# IMX7S_SENSORS___EXTERNAL_INTERFACES.net
KiCad netlist of a schematic drawn in Altium Designer
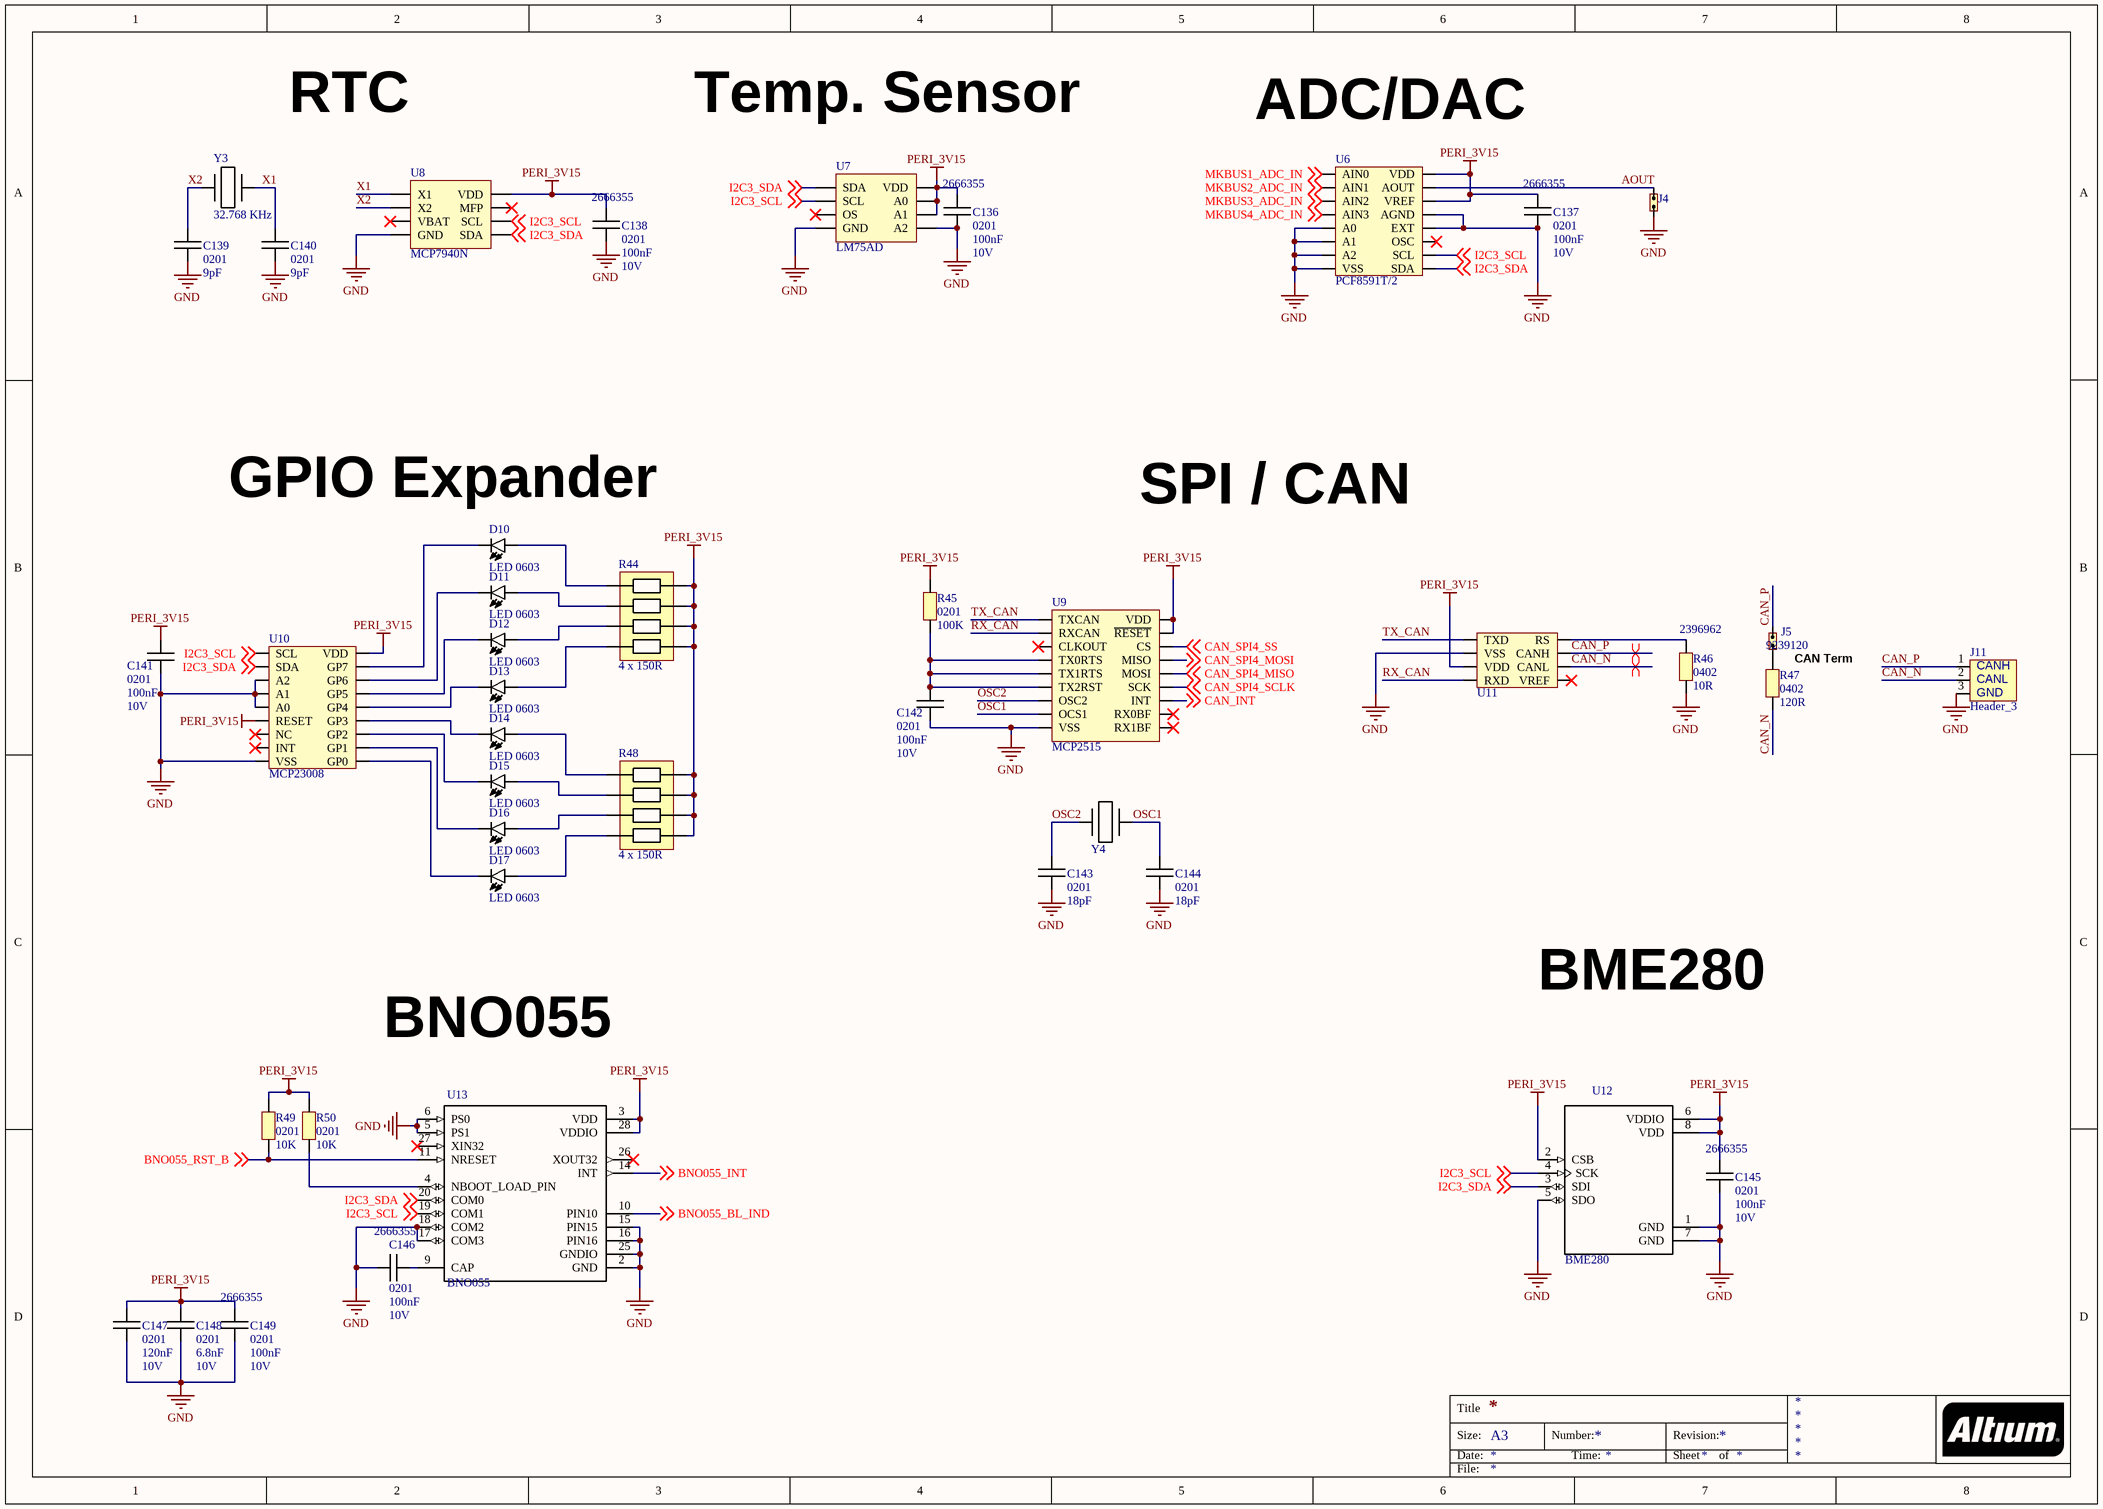
[diagram p0: IMX7S_SENSORS_&_EXTERNAL_INTERFACES.SchDoc]

(export (version "E")
  (design (tool "Eeschema 10.0.6"))
  (components
    (comp (ref "C136")
      (value "100nF")
      (footprint "C0201")
      (fields
        (field (name "PACKAGE") "0201")
        (field (name "VOLTAGE") "10V")
        (field (name "SUPPLIER PART NUMBER 1") "2666355")
        (field (name "TOLERANCE") "10%")
        (field (name "Comment") "C0201")
      )
      (libsource (lib "Schlib_IMX7") (part "C0201"))
    )
    (comp (ref "C137")
      (value "100nF")
      (footprint "C0201")
      (fields
        (field (name "PACKAGE") "0201")
        (field (name "VOLTAGE") "10V")
        (field (name "SUPPLIER PART NUMBER 1") "2666355")
        (field (name "TOLERANCE") "10%")
        (field (name "Comment") "C0201")
      )
      (libsource (lib "Schlib_IMX7") (part "C0201"))
    )
    (comp (ref "C138")
      (value "100nF")
      (footprint "C0201")
      (fields
        (field (name "PACKAGE") "0201")
        (field (name "VOLTAGE") "10V")
        (field (name "SUPPLIER PART NUMBER 1") "2666355")
        (field (name "TOLERANCE") "10%")
        (field (name "Comment") "C0201")
      )
      (libsource (lib "Schlib_IMX7") (part "C0201"))
    )
    (comp (ref "C139")
      (value "9pF")
      (footprint "C0201")
      (description "CAP CER 9PF 25V C0G 0201")
      (fields (field (name "PACKAGE") "0201") (field (name "VOLTAGE") "0V") (field (name "Comment") "C0201"))
      (libsource (lib "Schlib_IMX7") (part "C0201"))
    )
    (comp (ref "C140")
      (value "9pF")
      (footprint "C0201")
      (description "CAP CER 9PF 25V C0G 0201")
      (fields (field (name "PACKAGE") "0201") (field (name "VOLTAGE") "0V") (field (name "Comment") "C0201"))
      (libsource (lib "Schlib_IMX7") (part "C0201"))
    )
    (comp (ref "C141")
      (value "100nF")
      (footprint "C0201")
      (fields (field (name "PACKAGE") "0201") (field (name "VOLTAGE") "10V") (field (name "Comment") "C0201"))
      (libsource (lib "Schlib_IMX7") (part "C0201"))
    )
    (comp (ref "C142")
      (value "100nF")
      (footprint "C0201")
      (fields (field (name "PACKAGE") "0201") (field (name "VOLTAGE") "10V") (field (name "Comment") "C0201"))
      (libsource (lib "Schlib_IMX7") (part "C0201"))
    )
    (comp (ref "C143")
      (value "18pF")
      (footprint "C0201")
      (description "0201 18 pF 50 V ±2% Tolerance C0G/NP0 Multilayer Ceramic Capacitor")
      (fields (field (name "PACKAGE") "0201") (field (name "VOLTAGE") "10V") (field (name "TOLERANCE") "2%"))
      (libsource (lib "Schlib_IMX7") (part "C0201"))
    )
    (comp (ref "C144")
      (value "18pF")
      (footprint "C0201")
      (description "0201 18 pF 50 V ±2% Tolerance C0G/NP0 Multilayer Ceramic Capacitor")
      (fields (field (name "PACKAGE") "0201") (field (name "VOLTAGE") "10V") (field (name "TOLERANCE") "2%"))
      (libsource (lib "Schlib_IMX7") (part "C0201"))
    )
    (comp (ref "C145")
      (value "100nF")
      (footprint "C0201")
      (fields
        (field (name "PACKAGE") "0201")
        (field (name "VOLTAGE") "10V")
        (field (name "SUPPLIER PART NUMBER 1") "2666355")
        (field (name "TOLERANCE") "10%")
        (field (name "Comment") "C0201")
      )
      (libsource (lib "Schlib_IMX7") (part "C0201"))
    )
    (comp (ref "C146")
      (value "100nF")
      (footprint "C0201")
      (fields
        (field (name "PACKAGE") "0201")
        (field (name "VOLTAGE") "10V")
        (field (name "SUPPLIER PART NUMBER 1") "2666355")
        (field (name "TOLERANCE") "10%")
        (field (name "Comment") "C0201")
      )
      (libsource (lib "Schlib_IMX7") (part "C0201"))
    )
    (comp (ref "C147")
      (value "120nF")
      (footprint "C0201")
      (fields (field (name "PACKAGE") "0201") (field (name "VOLTAGE") "10V") (field (name "Comment") "C0201"))
      (libsource (lib "Schlib_IMX7") (part "C0201"))
    )
    (comp (ref "C148")
      (value "6.8nF")
      (footprint "C0201")
      (fields (field (name "PACKAGE") "0201") (field (name "VOLTAGE") "10V") (field (name "Comment") "C0201"))
      (libsource (lib "Schlib_IMX7") (part "C0201"))
    )
    (comp (ref "C149")
      (value "100nF")
      (footprint "C0201")
      (fields
        (field (name "PACKAGE") "0201")
        (field (name "VOLTAGE") "10V")
        (field (name "SUPPLIER PART NUMBER 1") "2666355")
        (field (name "TOLERANCE") "10%")
        (field (name "Comment") "C0201")
      )
      (libsource (lib "Schlib_IMX7") (part "C0201"))
    )
    (comp (ref "D10") (value "LED 0603") (footprint "D0603") (libsource (lib "Schlib_IMX7") (part "LED")))
    (comp (ref "D11") (value "LED 0603") (footprint "D0603") (libsource (lib "Schlib_IMX7") (part "LED")))
    (comp (ref "D12") (value "LED 0603") (footprint "D0603") (libsource (lib "Schlib_IMX7") (part "LED")))
    (comp (ref "D13") (value "LED 0603") (footprint "D0603") (libsource (lib "Schlib_IMX7") (part "LED")))
    (comp (ref "D14") (value "LED 0603") (footprint "D0603") (libsource (lib "Schlib_IMX7") (part "LED")))
    (comp (ref "D15") (value "LED 0603") (footprint "D0603") (libsource (lib "Schlib_IMX7") (part "LED")))
    (comp (ref "D16") (value "LED 0603") (footprint "D0603") (libsource (lib "Schlib_IMX7") (part "LED")))
    (comp (ref "D17") (value "LED 0603") (footprint "D0603") (libsource (lib "Schlib_IMX7") (part "LED")))
    (comp (ref "J4") (value "Jumper") (footprint "Header 2") (libsource (lib "Schlib_IMX7") (part "Jumper")))
    (comp (ref "J5") (value "Jumper") (footprint "Header 2") (libsource (lib "Schlib_IMX7") (part "Jumper")))
    (comp (ref "J11")
      (value "Header_3")
      (footprint "Header 3")
      (libsource (lib "Schlib_IMX7") (part "Header_3"))
    )
    (comp (ref "R44")
      (value "4 x 150R")
      (footprint "Reseau_R_1206")
      (libsource (lib "Schlib_IMX7") (part "Reseau_res"))
    )
    (comp (ref "R45")
      (value "100K")
      (footprint "R0201")
      (fields (field (name "PACKAGE") "0201") (field (name "VOLTAGE") "0V") (field (name "Comment") "R0201"))
      (libsource (lib "Schlib_IMX7") (part "R0201"))
    )
    (comp (ref "R46")
      (value "10R")
      (footprint "R0402")
      (fields
        (field (name "PACKAGE") "0402")
        (field (name "VOLTAGE") "0V")
        (field (name "SUPPLIER PART NUMBER 1") "2396962")
        (field (name "TOLERANCE") "1%")
        (field (name "Comment") "R0402")
      )
      (libsource (lib "Schlib_IMX7") (part "R0402"))
    )
    (comp (ref "R47")
      (value "120R")
      (footprint "R0402")
      (fields
        (field (name "PACKAGE") "0402")
        (field (name "VOLTAGE") "0V")
        (field (name "SUPPLIER PART NUMBER 1") "9239120")
        (field (name "TOLERANCE") "1%")
        (field (name "Comment") "R0402")
      )
      (libsource (lib "") (part "R0402_1"))
    )
    (comp (ref "R48")
      (value "4 x 150R")
      (footprint "Reseau_R_1206")
      (libsource (lib "Schlib_IMX7") (part "Reseau_res"))
    )
    (comp (ref "R49")
      (value "10K")
      (footprint "R0201")
      (fields (field (name "PACKAGE") "0201") (field (name "VOLTAGE") "0V") (field (name "Comment") "R0201"))
      (libsource (lib "Schlib_IMX7") (part "R0201"))
    )
    (comp (ref "R50")
      (value "10K")
      (footprint "R0201")
      (fields (field (name "PACKAGE") "0201") (field (name "VOLTAGE") "0V") (field (name "Comment") "R0201"))
      (libsource (lib "Schlib_IMX7") (part "R0201"))
    )
    (comp (ref "U6")
      (value "PCF8591T/2")
      (footprint "SOIC 16")
      (libsource (lib "Schlib_IMX7") (part "PCF8591T/2"))
    )
    (comp (ref "U7") (value "LM75AD") (footprint "SOIC 8") (libsource (lib "Schlib_IMX7") (part "LM75AD")))
    (comp (ref "U8")
      (value "MCP7940N")
      (footprint "SOIC 8")
      (libsource (lib "Schlib_IMX7") (part "MCP7940N"))
    )
    (comp (ref "U9") (value "MCP2515") (footprint "SOIC 18") (libsource (lib "Schlib_IMX7") (part "MCP2515")))
    (comp (ref "U10")
      (value "MCP23008")
      (footprint "SOIC 18")
      (libsource (lib "Schlib_IMX7") (part "MCP23008"))
    )
    (comp (ref "U11")
      (value "SN65HVD230DR")
      (footprint "SOIC 8")
      (libsource (lib "Schlib_IMX7") (part "SN65HVD230DR"))
    )
    (comp (ref "U12")
      (value "BME280")
      (footprint "PSON65P250X250X100-8N")
      (description "Integrated pressure, humidity and temperature sensor; 8-pin 2.5x2.5x0.93mm LGA")
      (fields (field (name "MF") "Bosch"))
      (libsource (lib "Schlib_IMX7") (part "BME280"))
    )
    (comp (ref "U13")
      (value "BNO055")
      (footprint "LGA28R50P4X10_380X520X100")
      (description "BNO055 9-axis Absolute Orientation Sensor _ SiP _ w/Sensors and Sensor Fusion")
      (fields (field (name "MF") "Bosch"))
      (libsource (lib "Schlib_IMX7") (part "BNO055"))
    )
    (comp (ref "Y3")
      (value "32.768 KHz")
      (footprint "ABS07")
      (libsource (lib "Schlib_IMX7") (part "Quartz 32.768"))
    )
    (comp (ref "Y4")
      (value "Quartz 8MHz")
      (footprint "HC49")
      (libsource (lib "Schlib_IMX7") (part "Quartz 8MHz"))
    )
  )
  (nets
    (net (code "1") (name "/AOUT") (class "Default")
      (node (ref "J4") (pin "2") (pinfunction "2_2") (pintype "passive"))
      (node (ref "U6") (pin "15") (pinfunction "AOUT_15") (pintype "passive"))
    )
    (net (code "2") (name "/CAN_N") (class "Default")
      (node (ref "J11") (pin "2") (pinfunction "2_2") (pintype "passive"))
      (node (ref "R47") (pin "1") (pinfunction "1_1") (pintype "passive"))
      (node (ref "U11") (pin "6") (pinfunction "CANL_6") (pintype "passive"))
    )
    (net (code "3") (name "/CAN_P") (class "Default")
      (node (ref "J11") (pin "1") (pinfunction "1_1") (pintype "passive"))
      (node (ref "J5") (pin "2") (pinfunction "2_2") (pintype "passive"))
      (node (ref "U11") (pin "7") (pinfunction "CANH_7") (pintype "passive"))
    )
    (net (code "4") (name "/OSC1") (class "Default")
      (node (ref "C144") (pin "2") (pinfunction "2_2") (pintype "passive"))
      (node (ref "U9") (pin "8") (pinfunction "OCS1_8") (pintype "passive"))
      (node (ref "Y4") (pin "2") (pintype "passive"))
    )
    (net (code "5") (name "/OSC2") (class "Default")
      (node (ref "C143") (pin "2") (pinfunction "2_2") (pintype "passive"))
      (node (ref "U9") (pin "7") (pinfunction "OSC2_7") (pintype "passive"))
      (node (ref "Y4") (pin "1") (pintype "passive"))
    )
    (net (code "6") (name "/RX_CAN") (class "Default")
      (node (ref "U11") (pin "4") (pinfunction "RXD_4") (pintype "passive"))
      (node (ref "U9") (pin "2") (pinfunction "RXCAN_2") (pintype "passive"))
    )
    (net (code "7") (name "/TX_CAN") (class "Default")
      (node (ref "U11") (pin "1") (pinfunction "TXD_1") (pintype "passive"))
      (node (ref "U9") (pin "1") (pinfunction "TXCAN_1") (pintype "passive"))
    )
    (net (code "8") (name "/X1") (class "Default")
      (node (ref "C140") (pin "2") (pinfunction "2_2") (pintype "passive"))
      (node (ref "U8") (pin "1") (pinfunction "X1_1") (pintype "passive"))
      (node (ref "Y3") (pin "2") (pintype "passive"))
    )
    (net (code "9") (name "/X2") (class "Default")
      (node (ref "C139") (pin "2") (pinfunction "2_2") (pintype "passive"))
      (node (ref "U8") (pin "2") (pinfunction "X2_2") (pintype "passive"))
      (node (ref "Y3") (pin "1") (pintype "passive"))
    )
    (net (code "10") (name "BNO055_BL_IND") (class "Default")
      (node (ref "U13") (pin "10") (pinfunction "PIN10_10") (pintype "power_in"))
    )
    (net (code "11") (name "BNO055_INT") (class "Default")
      (node (ref "U13") (pin "14") (pinfunction "INT_14") (pintype "output"))
    )
    (net (code "12") (name "BNO055_RST_B") (class "Default")
      (node (ref "R49") (pin "1") (pinfunction "1_1") (pintype "passive"))
      (node (ref "U13") (pin "11") (pinfunction "NRESET_11") (pintype "input"))
    )
    (net (code "13") (name "CAN_INT") (class "Default")
      (node (ref "U9") (pin "12") (pinfunction "INT_12") (pintype "passive"))
    )
    (net (code "14") (name "CAN_SPI4_MISO") (class "Default")
      (node (ref "U9") (pin "14") (pinfunction "MOSI_14") (pintype "passive"))
    )
    (net (code "15") (name "CAN_SPI4_MOSI") (class "Default")
      (node (ref "U9") (pin "15") (pinfunction "MISO_15") (pintype "passive"))
    )
    (net (code "16") (name "CAN_SPI4_SCLK") (class "Default")
      (node (ref "U9") (pin "13") (pinfunction "SCK_13") (pintype "passive"))
    )
    (net (code "17") (name "CAN_SPI4_SS") (class "Default")
      (node (ref "U9") (pin "16") (pinfunction "CS_16") (pintype "passive"))
    )
    (net (code "18") (name "GND") (class "Default")
      (node (ref "C136") (pin "2") (pinfunction "2_2") (pintype "passive"))
      (node (ref "C137") (pin "2") (pinfunction "2_2") (pintype "passive"))
      (node (ref "C138") (pin "2") (pinfunction "2_2") (pintype "passive"))
      (node (ref "C139") (pin "1") (pinfunction "1_1") (pintype "passive"))
      (node (ref "C140") (pin "1") (pinfunction "1_1") (pintype "passive"))
      (node (ref "C141") (pin "2") (pinfunction "2_2") (pintype "passive"))
      (node (ref "C142") (pin "2") (pinfunction "2_2") (pintype "passive"))
      (node (ref "C143") (pin "1") (pinfunction "1_1") (pintype "passive"))
      (node (ref "C144") (pin "1") (pinfunction "1_1") (pintype "passive"))
      (node (ref "C145") (pin "1") (pinfunction "1_1") (pintype "passive"))
      (node (ref "C146") (pin "2") (pinfunction "2_2") (pintype "passive"))
      (node (ref "C147") (pin "2") (pinfunction "2_2") (pintype "passive"))
      (node (ref "C148") (pin "2") (pinfunction "2_2") (pintype "passive"))
      (node (ref "C149") (pin "2") (pinfunction "2_2") (pintype "passive"))
      (node (ref "J11") (pin "3") (pinfunction "3_3") (pintype "passive"))
      (node (ref "J4") (pin "1") (pinfunction "1_1") (pintype "passive"))
      (node (ref "R46") (pin "2") (pinfunction "2_2") (pintype "passive"))
      (node (ref "U10") (pin "3") (pinfunction "A2_3") (pintype "passive"))
      (node (ref "U10") (pin "4") (pinfunction "A1_4") (pintype "passive"))
      (node (ref "U10") (pin "5") (pinfunction "A0_5") (pintype "passive"))
      (node (ref "U10") (pin "9") (pinfunction "VSS_9") (pintype "passive"))
      (node (ref "U11") (pin "2") (pinfunction "VSS_2") (pintype "passive"))
      (node (ref "U12") (pin "1") (pinfunction "GND_1") (pintype "power_in"))
      (node (ref "U12") (pin "5") (pinfunction "SDO_5") (pintype "bidirectional"))
      (node (ref "U12") (pin "7") (pinfunction "GND_7") (pintype "power_in"))
      (node (ref "U13") (pin "15") (pinfunction "PIN15_15") (pintype "power_in"))
      (node (ref "U13") (pin "16") (pinfunction "PIN16_16") (pintype "power_in"))
      (node (ref "U13") (pin "17") (pinfunction "COM3_17") (pintype "bidirectional"))
      (node (ref "U13") (pin "18") (pinfunction "COM2_18") (pintype "bidirectional"))
      (node (ref "U13") (pin "2") (pinfunction "GND_2") (pintype "power_in"))
      (node (ref "U13") (pin "25") (pinfunction "GNDIO_25") (pintype "power_in"))
      (node (ref "U13") (pin "5") (pinfunction "PS1_5") (pintype "input"))
      (node (ref "U13") (pin "6") (pinfunction "PS0_6") (pintype "input"))
      (node (ref "U6") (pin "12") (pinfunction "EXT_12") (pintype "passive"))
      (node (ref "U6") (pin "13") (pinfunction "AGND_13") (pintype "passive"))
      (node (ref "U6") (pin "5") (pinfunction "A0_5") (pintype "passive"))
      (node (ref "U6") (pin "6") (pinfunction "A1_6") (pintype "passive"))
      (node (ref "U6") (pin "7") (pinfunction "A2_7") (pintype "passive"))
      (node (ref "U6") (pin "8") (pinfunction "VSS_8") (pintype "passive"))
      (node (ref "U7") (pin "4") (pinfunction "GND_4") (pintype "passive"))
      (node (ref "U7") (pin "5") (pinfunction "A2_5") (pintype "passive"))
      (node (ref "U8") (pin "4") (pinfunction "GND_4") (pintype "passive"))
      (node (ref "U9") (pin "9") (pinfunction "VSS_9") (pintype "passive"))
    )
    (net (code "19") (name "I2C3_SCL") (class "Default")
      (node (ref "U10") (pin "1") (pinfunction "SCL_1") (pintype "passive"))
      (node (ref "U12") (pin "4") (pinfunction "SCK_4") (pintype "input"))
      (node (ref "U13") (pin "19") (pinfunction "COM1_19") (pintype "bidirectional"))
      (node (ref "U6") (pin "10") (pinfunction "SCL_10") (pintype "passive"))
      (node (ref "U7") (pin "2") (pinfunction "SCL_2") (pintype "passive"))
      (node (ref "U8") (pin "6") (pinfunction "SCL_6") (pintype "passive"))
    )
    (net (code "20") (name "I2C3_SDA") (class "Default")
      (node (ref "U10") (pin "2") (pinfunction "SDA_2") (pintype "passive"))
      (node (ref "U12") (pin "3") (pinfunction "SDI_3") (pintype "bidirectional"))
      (node (ref "U13") (pin "20") (pinfunction "COM0_20") (pintype "bidirectional"))
      (node (ref "U6") (pin "9") (pinfunction "SDA_9") (pintype "passive"))
      (node (ref "U7") (pin "1") (pinfunction "SDA_1") (pintype "passive"))
      (node (ref "U8") (pin "5") (pinfunction "SDA_5") (pintype "passive"))
    )
    (net (code "21") (name "MKBUS1_ADC_IN") (class "Default")
      (node (ref "U6") (pin "1") (pinfunction "AIN0_1") (pintype "passive"))
    )
    (net (code "22") (name "MKBUS2_ADC_IN") (class "Default")
      (node (ref "U6") (pin "2") (pinfunction "AIN1_2") (pintype "passive"))
    )
    (net (code "23") (name "MKBUS3_ADC_IN") (class "Default")
      (node (ref "U6") (pin "3") (pinfunction "AIN2_3") (pintype "passive"))
    )
    (net (code "24") (name "MKBUS4_ADC_IN") (class "Default")
      (node (ref "U6") (pin "4") (pinfunction "AIN3_4") (pintype "passive"))
    )
    (net (code "25") (name "Net-(D10-A)") (class "Default")
      (node (ref "D10") (pin "1") (pinfunction "A_1") (pintype "passive"))
      (node (ref "R44") (pin "5") (pinfunction "5_5") (pintype "passive"))
    )
    (net (code "26") (name "Net-(D10-K)") (class "Default")
      (node (ref "D10") (pin "2") (pinfunction "K_2") (pintype "passive"))
      (node (ref "U10") (pin "17") (pinfunction "GP7_17") (pintype "passive"))
    )
    (net (code "27") (name "Net-(D11-A)") (class "Default")
      (node (ref "D11") (pin "1") (pinfunction "A_1") (pintype "passive"))
      (node (ref "R44") (pin "6") (pinfunction "6_6") (pintype "passive"))
    )
    (net (code "28") (name "Net-(D11-K)") (class "Default")
      (node (ref "D11") (pin "2") (pinfunction "K_2") (pintype "passive"))
      (node (ref "U10") (pin "16") (pinfunction "GP6_16") (pintype "passive"))
    )
    (net (code "29") (name "Net-(D12-A)") (class "Default")
      (node (ref "D12") (pin "1") (pinfunction "A_1") (pintype "passive"))
      (node (ref "R44") (pin "7") (pinfunction "7_7") (pintype "passive"))
    )
    (net (code "30") (name "Net-(D12-K)") (class "Default")
      (node (ref "D12") (pin "2") (pinfunction "K_2") (pintype "passive"))
      (node (ref "U10") (pin "15") (pinfunction "GP5_15") (pintype "passive"))
    )
    (net (code "31") (name "Net-(D13-A)") (class "Default")
      (node (ref "D13") (pin "1") (pinfunction "A_1") (pintype "passive"))
      (node (ref "R44") (pin "8") (pinfunction "8_8") (pintype "passive"))
    )
    (net (code "32") (name "Net-(D13-K)") (class "Default")
      (node (ref "D13") (pin "2") (pinfunction "K_2") (pintype "passive"))
      (node (ref "U10") (pin "14") (pinfunction "GP4_14") (pintype "passive"))
    )
    (net (code "33") (name "Net-(D14-A)") (class "Default")
      (node (ref "D14") (pin "1") (pinfunction "A_1") (pintype "passive"))
      (node (ref "R48") (pin "5") (pinfunction "5_5") (pintype "passive"))
    )
    (net (code "34") (name "Net-(D14-K)") (class "Default")
      (node (ref "D14") (pin "2") (pinfunction "K_2") (pintype "passive"))
      (node (ref "U10") (pin "13") (pinfunction "GP3_13") (pintype "passive"))
    )
    (net (code "35") (name "Net-(D15-A)") (class "Default")
      (node (ref "D15") (pin "1") (pinfunction "A_1") (pintype "passive"))
      (node (ref "R48") (pin "6") (pinfunction "6_6") (pintype "passive"))
    )
    (net (code "36") (name "Net-(D15-K)") (class "Default")
      (node (ref "D15") (pin "2") (pinfunction "K_2") (pintype "passive"))
      (node (ref "U10") (pin "12") (pinfunction "GP2_12") (pintype "passive"))
    )
    (net (code "37") (name "Net-(D16-A)") (class "Default")
      (node (ref "D16") (pin "1") (pinfunction "A_1") (pintype "passive"))
      (node (ref "R48") (pin "7") (pinfunction "7_7") (pintype "passive"))
    )
    (net (code "38") (name "Net-(D16-K)") (class "Default")
      (node (ref "D16") (pin "2") (pinfunction "K_2") (pintype "passive"))
      (node (ref "U10") (pin "11") (pinfunction "GP1_11") (pintype "passive"))
    )
    (net (code "39") (name "Net-(D17-A)") (class "Default")
      (node (ref "D17") (pin "1") (pinfunction "A_1") (pintype "passive"))
      (node (ref "R48") (pin "8") (pinfunction "8_8") (pintype "passive"))
    )
    (net (code "40") (name "Net-(D17-K)") (class "Default")
      (node (ref "D17") (pin "2") (pinfunction "K_2") (pintype "passive"))
      (node (ref "U10") (pin "10") (pinfunction "GP0_10") (pintype "passive"))
    )
    (net (code "41") (name "Net-(J5-Pad1)") (class "Default")
      (node (ref "J5") (pin "1") (pinfunction "1_1") (pintype "passive"))
      (node (ref "R47") (pin "2") (pinfunction "2_2") (pintype "passive"))
    )
    (net (code "42") (name "Net-(U9-TX0RTS)") (class "Default")
      (node (ref "C142") (pin "1") (pinfunction "1_1") (pintype "passive"))
      (node (ref "R45") (pin "1") (pinfunction "1_1") (pintype "passive"))
      (node (ref "U9") (pin "4") (pinfunction "TX0RTS_4") (pintype "passive"))
      (node (ref "U9") (pin "5") (pinfunction "TX1RTS_5") (pintype "passive"))
      (node (ref "U9") (pin "6") (pinfunction "TX2RST_6") (pintype "passive"))
    )
    (net (code "43") (name "Net-(U11-RS)") (class "Default")
      (node (ref "R46") (pin "1") (pinfunction "1_1") (pintype "passive"))
      (node (ref "U11") (pin "8") (pinfunction "RS_8") (pintype "passive"))
    )
    (net (code "44") (name "Net-(U13-CAP)") (class "Default")
      (node (ref "C146") (pin "1") (pinfunction "1_1") (pintype "passive"))
      (node (ref "U13") (pin "9") (pinfunction "CAP_9") (pintype "passive"))
    )
    (net (code "45") (name "Net-(U13-NBOOT_LOAD_PIN)") (class "Default")
      (node (ref "R50") (pin "1") (pinfunction "1_1") (pintype "passive"))
      (node (ref "U13") (pin "4") (pinfunction "NBOOT_LOAD_PIN_4") (pintype "bidirectional"))
    )
    (net (code "46") (name "PERI_3V15") (class "Default")
      (node (ref "C136") (pin "1") (pinfunction "1_1") (pintype "passive"))
      (node (ref "C137") (pin "1") (pinfunction "1_1") (pintype "passive"))
      (node (ref "C138") (pin "1") (pinfunction "1_1") (pintype "passive"))
      (node (ref "C141") (pin "1") (pinfunction "1_1") (pintype "passive"))
      (node (ref "C145") (pin "2") (pinfunction "2_2") (pintype "passive"))
      (node (ref "C147") (pin "1") (pinfunction "1_1") (pintype "passive"))
      (node (ref "C148") (pin "1") (pinfunction "1_1") (pintype "passive"))
      (node (ref "C149") (pin "1") (pinfunction "1_1") (pintype "passive"))
      (node (ref "R44") (pin "1") (pinfunction "1_1") (pintype "passive"))
      (node (ref "R44") (pin "2") (pinfunction "2_2") (pintype "passive"))
      (node (ref "R44") (pin "3") (pinfunction "3_3") (pintype "passive"))
      (node (ref "R44") (pin "4") (pinfunction "4_4") (pintype "passive"))
      (node (ref "R45") (pin "2") (pinfunction "2_2") (pintype "passive"))
      (node (ref "R48") (pin "1") (pinfunction "1_1") (pintype "passive"))
      (node (ref "R48") (pin "2") (pinfunction "2_2") (pintype "passive"))
      (node (ref "R48") (pin "3") (pinfunction "3_3") (pintype "passive"))
      (node (ref "R48") (pin "4") (pinfunction "4_4") (pintype "passive"))
      (node (ref "R49") (pin "2") (pinfunction "2_2") (pintype "passive"))
      (node (ref "R50") (pin "2") (pinfunction "2_2") (pintype "passive"))
      (node (ref "U10") (pin "18") (pinfunction "VDD_18") (pintype "passive"))
      (node (ref "U10") (pin "6") (pinfunction "RESET_6") (pintype "passive"))
      (node (ref "U11") (pin "3") (pinfunction "VDD_3") (pintype "passive"))
      (node (ref "U12") (pin "2") (pinfunction "CSB_2") (pintype "input"))
      (node (ref "U12") (pin "6") (pinfunction "VDDIO_6") (pintype "power_in"))
      (node (ref "U12") (pin "8") (pinfunction "VDD_8") (pintype "power_in"))
      (node (ref "U13") (pin "28") (pinfunction "VDDIO_28") (pintype "power_in"))
      (node (ref "U13") (pin "3") (pinfunction "VDD_3") (pintype "power_in"))
      (node (ref "U6") (pin "14") (pinfunction "VREF_14") (pintype "passive"))
      (node (ref "U6") (pin "16") (pinfunction "VDD_16") (pintype "passive"))
      (node (ref "U7") (pin "6") (pinfunction "A1_6") (pintype "passive"))
      (node (ref "U7") (pin "7") (pinfunction "A0_7") (pintype "passive"))
      (node (ref "U7") (pin "8") (pinfunction "VDD_8") (pintype "passive"))
      (node (ref "U8") (pin "8") (pinfunction "VDD_8") (pintype "passive"))
      (node (ref "U9") (pin "17") (pinfunction "~{RESET}_17") (pintype "passive"))
      (node (ref "U9") (pin "18") (pinfunction "VDD_18") (pintype "passive"))
    )
    (net (code "47") (name "unconnected-(U6-OSC-Pad11)") (class "Default")
      (node (ref "U6") (pin "11") (pinfunction "OSC_11") (pintype "passive+no_connect"))
    )
    (net (code "48") (name "unconnected-(U7-OS-Pad3)") (class "Default")
      (node (ref "U7") (pin "3") (pinfunction "OS_3") (pintype "passive+no_connect"))
    )
    (net (code "49") (name "unconnected-(U8-MFP-Pad7)") (class "Default")
      (node (ref "U8") (pin "7") (pinfunction "MFP_7") (pintype "passive+no_connect"))
    )
    (net (code "50") (name "unconnected-(U8-VBAT-Pad3)") (class "Default")
      (node (ref "U8") (pin "3") (pinfunction "VBAT_3") (pintype "passive+no_connect"))
    )
    (net (code "51") (name "unconnected-(U9-CLKOUT-Pad3)") (class "Default")
      (node (ref "U9") (pin "3") (pinfunction "CLKOUT_3") (pintype "passive+no_connect"))
    )
    (net (code "52") (name "unconnected-(U9-RX0BF-Pad11)") (class "Default")
      (node (ref "U9") (pin "11") (pinfunction "RX0BF_11") (pintype "passive+no_connect"))
    )
    (net (code "53") (name "unconnected-(U9-RX1BF-Pad10)") (class "Default")
      (node (ref "U9") (pin "10") (pinfunction "RX1BF_10") (pintype "passive+no_connect"))
    )
    (net (code "54") (name "unconnected-(U10-INT-Pad8)") (class "Default")
      (node (ref "U10") (pin "8") (pinfunction "INT_8") (pintype "passive+no_connect"))
    )
    (net (code "55") (name "unconnected-(U10-NC-Pad7)") (class "Default")
      (node (ref "U10") (pin "7") (pinfunction "NC_7") (pintype "passive+no_connect"))
    )
    (net (code "56") (name "unconnected-(U11-VREF-Pad5)") (class "Default")
      (node (ref "U11") (pin "5") (pinfunction "VREF_5") (pintype "passive+no_connect"))
    )
    (net (code "57") (name "unconnected-(U13-XIN32-Pad27)") (class "Default")
      (node (ref "U13") (pin "27") (pinfunction "XIN32_27") (pintype "input+no_connect"))
    )
    (net (code "58") (name "unconnected-(U13-XOUT32-Pad26)") (class "Default")
      (node (ref "U13") (pin "26") (pinfunction "XOUT32_26") (pintype "output+no_connect"))
    )
  )
)
